# LM3150_BuckConverter.net
KiCad netlist of a schematic drawn in Altium Designer
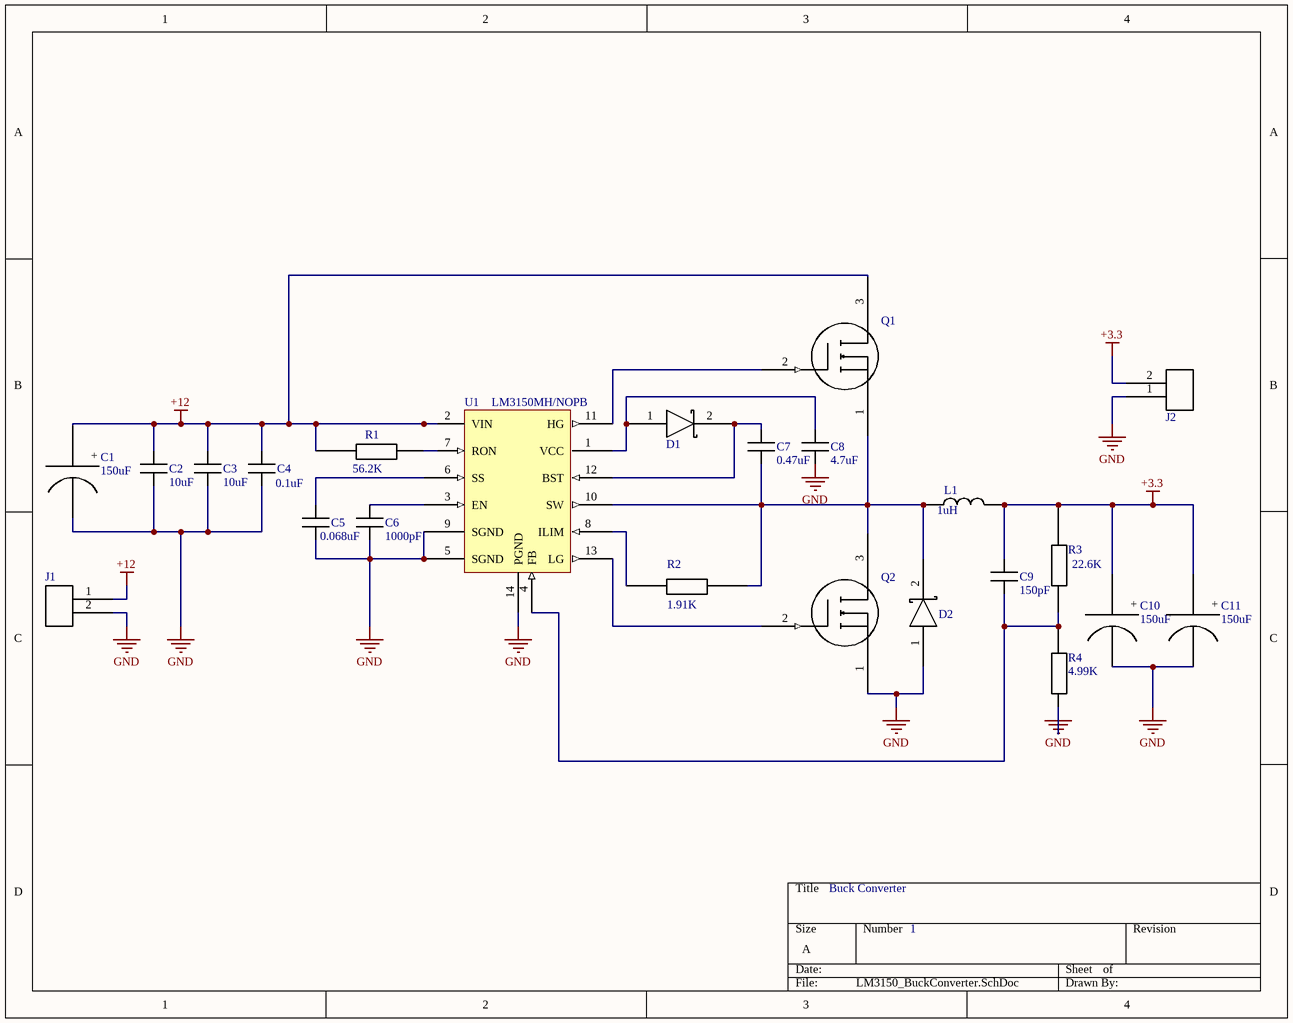
[diagram p0: LM3150_BuckConverter.SchDoc]

(export (version "E")
  (design (tool "Eeschema 10.0.6"))
  (components
    (comp (ref "C1")
      (value "150uF")
      (footprint "Cap860010675016")
      (description "CAP ALUM 150UF 20% 63V RADIAL")
      (fields
        (field (name "MANUFACTURER") "Würth Elektronik")
        (field (name "MANUFACTURER PART NUMBER") "860010675016")
      )
      (libsource (lib "LM3150_BuckConverter") (part "Polarized_Cap"))
    )
    (comp (ref "C2")
      (value "10uF")
      (footprint "C1206")
      (description "CAP CER 10UF 25V X7R 1206")
      (fields
        (field (name "MANUFACTURER") "Samsung Electro-Mechanics")
        (field (name "MANUFACTURER PART NUMBER") "CL31B106KAHVPNE")
      )
      (libsource (lib "LM3150_BuckConverter") (part "Capacitor"))
    )
    (comp (ref "C3")
      (value "10uF")
      (footprint "C1206")
      (description "CAP CER 10UF 25V X7R 1206")
      (fields
        (field (name "MANUFACTURER") "Samsung Electro-Mechanics")
        (field (name "MANUFACTURER PART NUMBER") "CL31B106KAHVPNE")
      )
      (libsource (lib "LM3150_BuckConverter") (part "Capacitor"))
    )
    (comp (ref "C4")
      (value "0.1uF")
      (footprint "C0805")
      (description "CAP CER 0.1UF 50V X7R 0805")
      (fields
        (field (name "MANUFACTURER") "AVX Corporation")
        (field (name "MANUFACTURER PART NUMBER") "08055C104KAT2A")
      )
      (libsource (lib "LM3150_BuckConverter") (part "Capacitor"))
    )
    (comp (ref "C5")
      (value "0.068uF")
      (footprint "C0805")
      (description "CAP CER 0.068UF 25V X7R 0805")
      (fields
        (field (name "MANUFACTURER") "YAGEO")
        (field (name "MANUFACTURER PART NUMBER") "CC0805KRX7R8BB683")
      )
      (libsource (lib "LM3150_BuckConverter") (part "Capacitor"))
    )
    (comp (ref "C6")
      (value "1000pF")
      (footprint "C0805")
      (description "CAP CER 1000PF 50V X7R 0805")
      (fields
        (field (name "MANUFACTURER") "Samsung Electro-Mechanics")
        (field (name "MANUFACTURER PART NUMBER") "CL21B102KBCNNNC")
      )
      (libsource (lib "LM3150_BuckConverter") (part "Capacitor"))
    )
    (comp (ref "C7")
      (value "0.47uF")
      (footprint "C0805")
      (description "CAP CER 0.47UF 16V X7R 0805")
      (fields
        (field (name "MANUFACTURER") "Samsung Electro-Mechanics")
        (field (name "MANUFACTURER PART NUMBER") "CL21B474KOFNNNE")
      )
      (libsource (lib "LM3150_BuckConverter") (part "Capacitor"))
    )
    (comp (ref "C8")
      (value "4.7uF")
      (footprint "C0805")
      (description "CAP CER 4.7UF 16V X7R 0805")
      (fields
        (field (name "MANUFACTURER") "Taiyo Yuden")
        (field (name "MANUFACTURER PART NUMBER") "EMK212B7475KG-T")
      )
      (libsource (lib "LM3150_BuckConverter") (part "Capacitor"))
    )
    (comp (ref "C9")
      (value "150pF")
      (footprint "C0805")
      (description "CAP CER 150PF 50V C0G/NPO 0805")
      (fields
        (field (name "MANUFACTURER") "YAGEO")
        (field (name "MANUFACTURER PART NUMBER") "CC0805JRNPO9BN151")
      )
      (libsource (lib "LM3150_BuckConverter") (part "Capacitor"))
    )
    (comp (ref "C10")
      (value "150uF")
      (footprint "A765EB157M0JLAE020")
      (description "CAP ALUM POLY 150UF 20% 6.3V SMD")
      (fields
        (field (name "MANUFACTURER") "KEMET")
        (field (name "MANUFACTURER PART NUMBER") "A765EB157M0JLAE020")
      )
      (libsource (lib "LM3150_BuckConverter") (part "Polarized_Cap"))
    )
    (comp (ref "C11")
      (value "150uF")
      (footprint "A765EB157M0JLAE020")
      (description "CAP ALUM POLY 150UF 20% 6.3V SMD")
      (fields
        (field (name "MANUFACTURER") "KEMET")
        (field (name "MANUFACTURER PART NUMBER") "A765EB157M0JLAE020")
      )
      (libsource (lib "LM3150_BuckConverter") (part "Polarized_Cap"))
    )
    (comp (ref "D1")
      (value "Dbst")
      (footprint "CUS08F30")
      (description "DIODE SCHOTTKY 30V 800MA USC")
      (fields
        (field (name "MANUFACTURER PART NUMBER") "CUS08F30,H3F")
        (field (name "MANUFACTURER") "Toshiba Semiconductor and Storage")
      )
      (libsource (lib "LM3150_BuckConverter") (part "Schottky"))
    )
    (comp (ref "D2")
      (value "Schottky")
      (footprint "CUS08F30")
      (description "DIODE SCHOTTKY 30V 800MA USC")
      (fields
        (field (name "MANUFACTURER PART NUMBER") "CUS08F30,H3F")
        (field (name "MANUFACTURER") "Toshiba Semiconductor and Storage")
      )
      (libsource (lib "LM3150_BuckConverter") (part "Schottky"))
    )
    (comp (ref "J1")
      (value "Input")
      (footprint "TB006-508-02BE")
      (description "TERMINAL BLOCK, SCREW TYPE, 5.08")
      (fields
        (field (name "MANUFACTURER") "CUI Devices")
        (field (name "MANUFACTURER PART NUMBER") "TB006-508-02BE")
      )
      (libsource (lib "LM3150_BuckConverter") (part "Terminal_Block"))
    )
    (comp (ref "J2")
      (value "Output")
      (footprint "TB006-508-02BE")
      (description "TERMINAL BLOCK, SCREW TYPE, 5.08")
      (fields
        (field (name "MANUFACTURER") "CUI Devices")
        (field (name "MANUFACTURER PART NUMBER") "TB006-508-02BE")
      )
      (libsource (lib "LM3150_BuckConverter") (part "Terminal_Block"))
    )
    (comp (ref "L1")
      (value "1uH")
      (footprint "MPCV1060L1R0")
      (description "FIXED IND 1UH 26A 1.87 MOHM SMD")
      (fields (field (name "MANUFACTURER") "KEMET") (field (name "MANUFACTURER PART NUMBER") "MPCV1060L1R0"))
      (libsource (lib "LM3150_BuckConverter") (part "Coil"))
    )
    (comp (ref "Q1")
      (value "Mosfet")
      (footprint "CSD18540Q5B")
      (description "MOSFET N-CH 60V 100A 8VSON")
      (fields
        (field (name "MANUFACTURER PART NUMBER") "CSD18540Q5B")
        (field (name "MANUFACTURER") "Texas Instruments")
      )
      (libsource (lib "LM3150_BuckConverter") (part "Mosfet"))
    )
    (comp (ref "Q2")
      (value "Mosfet")
      (footprint "CSD18540Q5B")
      (description "MOSFET N-CH 60V 100A 8VSON")
      (fields
        (field (name "MANUFACTURER PART NUMBER") "CSD18540Q5B")
        (field (name "MANUFACTURER") "Texas Instruments")
      )
      (libsource (lib "LM3150_BuckConverter") (part "Mosfet"))
    )
    (comp (ref "R1")
      (value "56.2K")
      (footprint "R0805")
      (description "RES 56.2K OHM 1% 1/8W 0805")
      (fields
        (field (name "MANUFACTURER") "Stackpole Electronics Inc")
        (field (name "MANUFACTURER PART NUMBER") "RMCF0805FT56K2")
      )
      (libsource (lib "LM3150_BuckConverter") (part "Resistor"))
    )
    (comp (ref "R2")
      (value "1.91K")
      (footprint "R0805")
      (description "RES SMD 1.91K OHM 1% 1/8W 0805")
      (fields
        (field (name "MANUFACTURER") "YAGEO")
        (field (name "MANUFACTURER PART NUMBER") "RC0805FR-071K91L")
      )
      (libsource (lib "LM3150_BuckConverter") (part "Resistor"))
    )
    (comp (ref "R3")
      (value "22.6K")
      (footprint "R0805")
      (description "RES SMD 22.6K OHM 1% 1/8W 0805")
      (fields
        (field (name "MANUFACTURER") "Vishay Dale")
        (field (name "MANUFACTURER PART NUMBER") "CRCW080522K6FKEA")
      )
      (libsource (lib "LM3150_BuckConverter") (part "Resistor"))
    )
    (comp (ref "R4")
      (value "4.99K")
      (footprint "R0805")
      (description "RES 4.99K OHM 1% 1/8W 0805")
      (fields
        (field (name "MANUFACTURER") "Stackpole Electronics Inc")
        (field (name "MANUFACTURER PART NUMBER") "RMCF0805FT4K99")
      )
      (libsource (lib "LM3150_BuckConverter") (part "Resistor"))
    )
    (comp (ref "U1")
      (value "LM3150MH/NOPB")
      (footprint "LM3150MH/NOPB")
      (description "IC REG CTRLR BUCK 14TSSOP")
      (fields
        (field (name "MANUFACTURER") "Texas Instruments")
        (field (name "MANUFACTURER PART NUMBER") "LM3150MHNOPB")
      )
      (libsource (lib "LM3150_BuckConverter") (part "LM3150MH/NOPB"))
    )
  )
  (nets
    (net (code "1") (name "+3.3") (class "Default")
      (node (ref "C10") (pin "1") (pinfunction "+_1") (pintype "passive"))
      (node (ref "C11") (pin "1") (pinfunction "+_1") (pintype "passive"))
      (node (ref "C9") (pin "2") (pinfunction "2_2") (pintype "passive"))
      (node (ref "J2") (pin "2") (pinfunction "*_2") (pintype "passive"))
      (node (ref "L1") (pin "2") (pinfunction "2_2") (pintype "passive"))
      (node (ref "R3") (pin "1") (pinfunction "1_1") (pintype "passive"))
    )
    (net (code "2") (name "+12") (class "Default")
      (node (ref "C1") (pin "1") (pinfunction "+_1") (pintype "passive"))
      (node (ref "C2") (pin "2") (pinfunction "2_2") (pintype "passive"))
      (node (ref "C3") (pin "2") (pinfunction "2_2") (pintype "passive"))
      (node (ref "C4") (pin "2") (pinfunction "2_2") (pintype "passive"))
      (node (ref "J1") (pin "1") (pinfunction "*_1") (pintype "passive"))
      (node (ref "Q1") (pin "3") (pinfunction "D_3") (pintype "passive"))
      (node (ref "R1") (pin "2") (pinfunction "2_2") (pintype "passive"))
      (node (ref "U1") (pin "2") (pinfunction "VIN_2") (pintype "power_in"))
    )
    (net (code "3") (name "GND") (class "Default")
      (node (ref "C1") (pin "2") (pinfunction "-_2") (pintype "passive"))
      (node (ref "C10") (pin "2") (pinfunction "-_2") (pintype "passive"))
      (node (ref "C11") (pin "2") (pinfunction "-_2") (pintype "passive"))
      (node (ref "C2") (pin "1") (pinfunction "1_1") (pintype "passive"))
      (node (ref "C3") (pin "1") (pinfunction "1_1") (pintype "passive"))
      (node (ref "C4") (pin "1") (pinfunction "1_1") (pintype "passive"))
      (node (ref "C5") (pin "1") (pinfunction "1_1") (pintype "passive"))
      (node (ref "C6") (pin "1") (pinfunction "1_1") (pintype "passive"))
      (node (ref "C8") (pin "2") (pinfunction "2_2") (pintype "passive"))
      (node (ref "D2") (pin "1") (pinfunction "-_1") (pintype "passive"))
      (node (ref "J1") (pin "2") (pinfunction "*_2") (pintype "passive"))
      (node (ref "J2") (pin "1") (pinfunction "*_1") (pintype "passive"))
      (node (ref "Q2") (pin "1") (pinfunction "S_1") (pintype "passive"))
      (node (ref "R4") (pin "2") (pinfunction "2_2") (pintype "passive"))
      (node (ref "U1") (pin "14") (pinfunction "PGND_14") (pintype "power_in"))
      (node (ref "U1") (pin "5") (pinfunction "SGND_5") (pintype "power_in"))
      (node (ref "U1") (pin "9") (pinfunction "SGND_9") (pintype "power_in"))
    )
    (net (code "4") (name "Net-(D1-+)") (class "Default")
      (node (ref "C7") (pin "1") (pinfunction "1_1") (pintype "passive"))
      (node (ref "D1") (pin "2") (pinfunction "+_2") (pintype "passive"))
      (node (ref "U1") (pin "12") (pinfunction "BST_12") (pintype "input"))
    )
    (net (code "5") (name "Net-(D1--)") (class "Default")
      (node (ref "C8") (pin "1") (pinfunction "1_1") (pintype "passive"))
      (node (ref "D1") (pin "1") (pinfunction "-_1") (pintype "passive"))
      (node (ref "U1") (pin "1") (pinfunction "VCC_1") (pintype "power_in"))
    )
    (net (code "6") (name "Net-(D2-+)") (class "Default")
      (node (ref "C7") (pin "2") (pinfunction "2_2") (pintype "passive"))
      (node (ref "D2") (pin "2") (pinfunction "+_2") (pintype "passive"))
      (node (ref "L1") (pin "1") (pinfunction "1_1") (pintype "passive"))
      (node (ref "Q1") (pin "1") (pinfunction "S_1") (pintype "passive"))
      (node (ref "Q2") (pin "3") (pinfunction "D_3") (pintype "passive"))
      (node (ref "R2") (pin "1") (pinfunction "1_1") (pintype "passive"))
      (node (ref "U1") (pin "10") (pinfunction "SW_10") (pintype "output"))
    )
    (net (code "7") (name "Net-(Q1-G)") (class "Default")
      (node (ref "Q1") (pin "2") (pinfunction "G_2") (pintype "input"))
      (node (ref "U1") (pin "11") (pinfunction "HG_11") (pintype "output"))
    )
    (net (code "8") (name "Net-(Q2-G)") (class "Default")
      (node (ref "Q2") (pin "2") (pinfunction "G_2") (pintype "input"))
      (node (ref "U1") (pin "13") (pinfunction "LG_13") (pintype "output"))
    )
    (net (code "9") (name "Net-(U1-EN)") (class "Default")
      (node (ref "C6") (pin "2") (pinfunction "2_2") (pintype "passive"))
      (node (ref "U1") (pin "3") (pinfunction "EN_3") (pintype "input"))
    )
    (net (code "10") (name "Net-(U1-FB)") (class "Default")
      (node (ref "C9") (pin "1") (pinfunction "1_1") (pintype "passive"))
      (node (ref "R3") (pin "2") (pinfunction "2_2") (pintype "passive"))
      (node (ref "R4") (pin "1") (pinfunction "1_1") (pintype "passive"))
      (node (ref "U1") (pin "4") (pinfunction "FB_4") (pintype "input"))
    )
    (net (code "11") (name "Net-(U1-ILIM)") (class "Default")
      (node (ref "R2") (pin "2") (pinfunction "2_2") (pintype "passive"))
      (node (ref "U1") (pin "8") (pinfunction "ILIM_8") (pintype "input"))
    )
    (net (code "12") (name "Net-(U1-RON)") (class "Default")
      (node (ref "R1") (pin "1") (pinfunction "1_1") (pintype "passive"))
      (node (ref "U1") (pin "7") (pinfunction "RON_7") (pintype "input"))
    )
    (net (code "13") (name "Net-(U1-SS)") (class "Default")
      (node (ref "C5") (pin "2") (pinfunction "2_2") (pintype "passive"))
      (node (ref "U1") (pin "6") (pinfunction "SS_6") (pintype "input"))
    )
  )
)
